# SIM808_SmartLock.net
KiCad netlist of a schematic drawn in Altium Designer
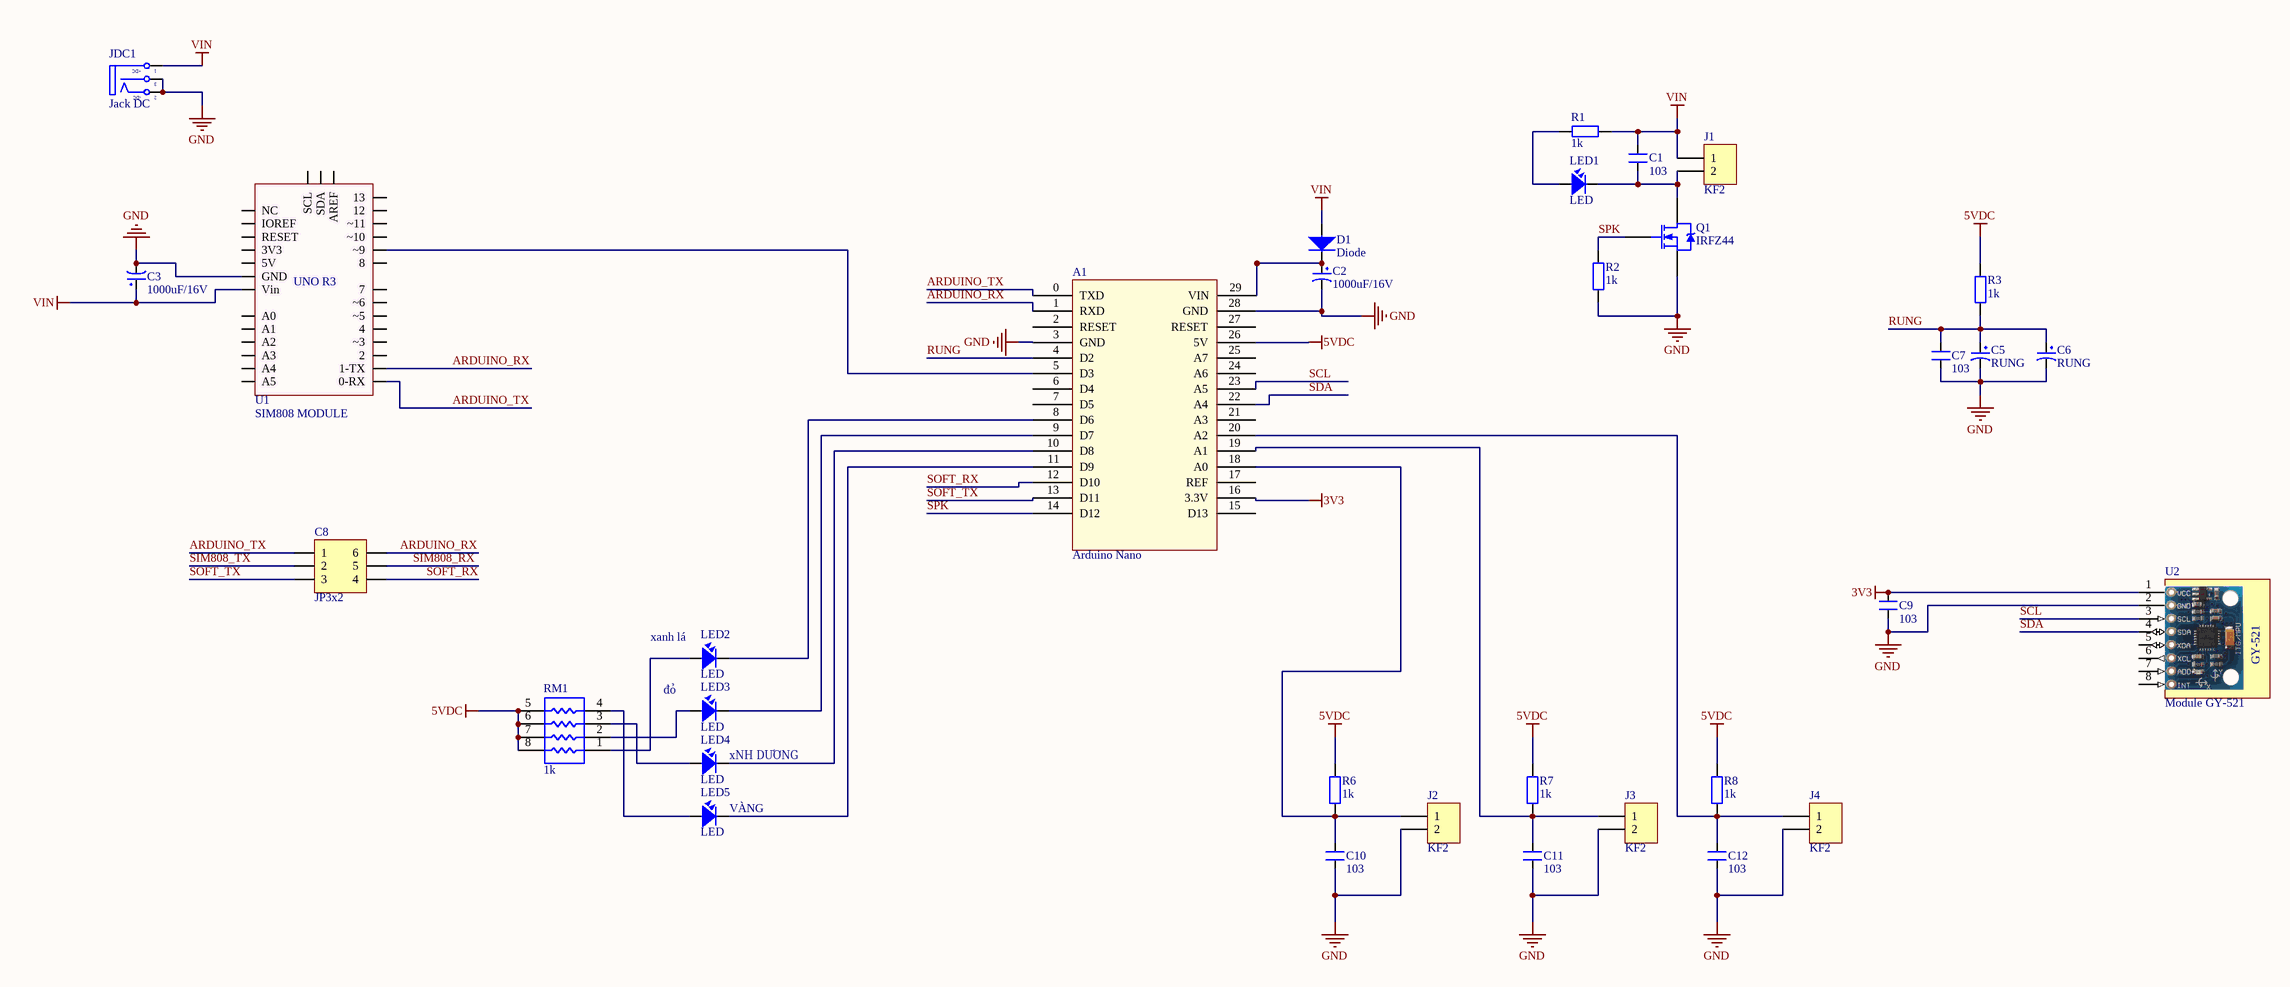
[diagram p0: SIM808_SmartLock.SchDoc]

(export (version "E")
  (design (tool "Eeschema 10.0.6"))
  (components
    (comp (ref "A1")
      (value "Arduino Nano")
      (footprint "Arduino Nano")
      (libsource (lib "OBIT_TESLA") (part "Arduino Nano"))
    )
    (comp (ref "C1")
      (value "103")
      (footprint "SM-0805")
      (description "Cap SMD")
      (libsource (lib "OBIT_TESLA") (part "CM"))
    )
    (comp (ref "C2")
      (value "1000uF/16V")
      (footprint "CP1.5/3.4")
      (description "Cap 1000uF/16V - 220uF/50V")
      (libsource (lib "OBIT_TESLA") (part "CP4"))
    )
    (comp (ref "C3")
      (value "1000uF/16V")
      (footprint "CP1.5/3.4")
      (description "Cap 1000uF/16V - 220uF/50V")
      (libsource (lib "OBIT_TESLA") (part "CP4"))
    )
    (comp (ref "C5")
      (value "RUNG")
      (footprint "CP1.5/3.4")
      (description "Cap 1000uF/16V - 220uF/50V")
      (libsource (lib "OBIT_TESLA") (part "CP4"))
    )
    (comp (ref "C6")
      (value "RUNG")
      (footprint "CP1.5/3.4")
      (description "Cap 1000uF/16V - 220uF/50V")
      (libsource (lib "OBIT_TESLA") (part "CP4"))
    )
    (comp (ref "C7")
      (value "103")
      (footprint "SM-0805")
      (description "Cap SMD")
      (libsource (lib "OBIT_TESLA") (part "CM"))
    )
    (comp (ref "C8")
      (value "JP3x2")
      (footprint "JP3-D2T")
      (description "WR-PHD 2.54 mm Dual Socket Header")
      (fields
        (field (name "MANUFACTURER") "Würth Elektronik eiSos GmbH")
        (field (name "PARTNO") "61300621821")
        (field (name "CREATED BY") "Karrer Zheng")
      )
      (libsource (lib "OBIT_TESLA") (part "JP3x2"))
    )
    (comp (ref "C9")
      (value "103")
      (footprint "SM-0805")
      (description "Cap SMD")
      (libsource (lib "OBIT_TESLA") (part "CM"))
    )
    (comp (ref "C10")
      (value "103")
      (footprint "SM-0805")
      (description "Cap SMD")
      (libsource (lib "OBIT_TESLA") (part "CM"))
    )
    (comp (ref "C11")
      (value "103")
      (footprint "SM-0805")
      (description "Cap SMD")
      (libsource (lib "OBIT_TESLA") (part "CM"))
    )
    (comp (ref "C12")
      (value "103")
      (footprint "SM-0805")
      (description "Cap SMD")
      (libsource (lib "OBIT_TESLA") (part "CM"))
    )
    (comp (ref "D1") (value "Diode") (footprint "DIO-SMD-106") (libsource (lib "OBIT_TESLA") (part "Diode")))
    (comp (ref "J1")
      (value "KF2")
      (footprint "KF2-5.08")
      (fields
        (field (name "MANUFACTURER") "Würth Elektronik eiSos GmbH")
        (field (name "PARTNO") "691103110002")
        (field (name "CREATED BY") "Karrer Zheng")
      )
      (libsource (lib "OBIT_TESLA") (part "KF2"))
    )
    (comp (ref "J2")
      (value "KF2")
      (footprint "KF2-5.08")
      (fields
        (field (name "MANUFACTURER") "Würth Elektronik eiSos GmbH")
        (field (name "PARTNO") "691103110002")
        (field (name "CREATED BY") "Karrer Zheng")
      )
      (libsource (lib "OBIT_TESLA") (part "KF2"))
    )
    (comp (ref "J3")
      (value "KF2")
      (footprint "KF2-5.08")
      (fields
        (field (name "MANUFACTURER") "Würth Elektronik eiSos GmbH")
        (field (name "PARTNO") "691103110002")
        (field (name "CREATED BY") "Karrer Zheng")
      )
      (libsource (lib "OBIT_TESLA") (part "KF2"))
    )
    (comp (ref "J4")
      (value "KF2")
      (footprint "KF2-5.08")
      (fields
        (field (name "MANUFACTURER") "Würth Elektronik eiSos GmbH")
        (field (name "PARTNO") "691103110002")
        (field (name "CREATED BY") "Karrer Zheng")
      )
      (libsource (lib "OBIT_TESLA") (part "KF2"))
    )
    (comp (ref "JDC1") (value "Jack DC") (footprint "DC0") (libsource (lib "OBIT_TESLA") (part "JACK_DC")))
    (comp (ref "LED1") (value "LED") (footprint "LED-5-BLUE") (libsource (lib "OBIT_TESLA") (part "LED")))
    (comp (ref "LED2") (value "LED") (footprint "LED-5-BLUE") (libsource (lib "OBIT_TESLA") (part "LED")))
    (comp (ref "LED3") (value "LED") (footprint "LED-5-BLUE") (libsource (lib "OBIT_TESLA") (part "LED")))
    (comp (ref "LED4") (value "LED") (footprint "LED-5-BLUE") (libsource (lib "OBIT_TESLA") (part "LED")))
    (comp (ref "LED5") (value "LED") (footprint "LED-5-BLUE") (libsource (lib "OBIT_TESLA") (part "LED")))
    (comp (ref "Q1") (value "IRFZ44") (footprint "TO252-123") (libsource (lib "OBIT_TESLA") (part "IRFZ44")))
    (comp (ref "R1")
      (value "1k")
      (footprint "RES-1/4W")
      (description "Resistor R1/4W")
      (libsource (lib "OBIT_TESLA") (part "R"))
    )
    (comp (ref "R2")
      (value "1k")
      (footprint "RES-1/4W")
      (description "Resistor R1/4W")
      (libsource (lib "OBIT_TESLA") (part "R"))
    )
    (comp (ref "R3")
      (value "1k")
      (footprint "RES-1/4W")
      (description "Resistor R1/4W")
      (libsource (lib "OBIT_TESLA") (part "R"))
    )
    (comp (ref "R6")
      (value "1k")
      (footprint "RES-1/4W")
      (description "Resistor R1/4W")
      (libsource (lib "OBIT_TESLA") (part "R"))
    )
    (comp (ref "R7")
      (value "1k")
      (footprint "RES-1/4W")
      (description "Resistor R1/4W")
      (libsource (lib "OBIT_TESLA") (part "R"))
    )
    (comp (ref "R8")
      (value "1k")
      (footprint "RES-1/4W")
      (description "Resistor R1/4W")
      (libsource (lib "OBIT_TESLA") (part "R"))
    )
    (comp (ref "RM1") (value "1k") (footprint "RN4-0805") (libsource (lib "OBIT_TESLA") (part "ResPack")))
    (comp (ref "U1")
      (value "SIM808 MODULE")
      (footprint "Arduino UNO R3")
      (description "ARDUINO  R3 ATMEGA328, ARDUINO UNO, EVAL BOARD")
      (libsource (lib "MCU") (part "KIT ARDUINO R3"))
    )
    (comp (ref "U2")
      (value "Module GY-521")
      (footprint "MODULE GY-9150")
      (description "MPU 6050")
      (libsource (lib "AltiumLibraryTieuBao (1)") (part "Module GY-521"))
    )
  )
  (nets
    (net (code "1") (name "/ARDUINO_RX") (class "Default")
      (node (ref "A1") (pin "1") (pinfunction "RXD_1") (pintype "passive"))
      (node (ref "C8") (pin "6") (pinfunction "6_6") (pintype "passive"))
      (node (ref "U1") (pin "1-TX") (pinfunction "1-TX_1-TX") (pintype "passive"))
    )
    (net (code "2") (name "/ARDUINO_TX") (class "Default")
      (node (ref "A1") (pin "0") (pinfunction "TXD_0") (pintype "passive"))
      (node (ref "C8") (pin "1") (pinfunction "1_1") (pintype "passive"))
      (node (ref "U1") (pin "0-RX") (pinfunction "0-RX_0-RX") (pintype "passive"))
    )
    (net (code "3") (name "/RUNG") (class "Default")
      (node (ref "A1") (pin "4") (pinfunction "D2_4") (pintype "passive"))
      (node (ref "C5") (pin "1") (pinfunction "1_1") (pintype "passive"))
      (node (ref "C6") (pin "1") (pinfunction "1_1") (pintype "passive"))
      (node (ref "C7") (pin "2") (pinfunction "2_2") (pintype "passive"))
      (node (ref "R3") (pin "1") (pinfunction "1_1") (pintype "passive"))
    )
    (net (code "4") (name "/SCL") (class "Default")
      (node (ref "A1") (pin "23") (pinfunction "A5_23") (pintype "passive"))
      (node (ref "U2") (pin "3") (pinfunction "SCL_3") (pintype "input"))
    )
    (net (code "5") (name "/SDA") (class "Default")
      (node (ref "A1") (pin "22") (pinfunction "A4_22") (pintype "passive"))
      (node (ref "U2") (pin "4") (pinfunction "SDA_4") (pintype "bidirectional"))
    )
    (net (code "6") (name "/SIM808_RX") (class "Default")
      (node (ref "C8") (pin "5") (pinfunction "5_5") (pintype "passive"))
    )
    (net (code "7") (name "/SIM808_TX") (class "Default")
      (node (ref "C8") (pin "2") (pinfunction "2_2") (pintype "passive"))
    )
    (net (code "8") (name "/SOFT_RX") (class "Default")
      (node (ref "A1") (pin "12") (pinfunction "D10_12") (pintype "passive"))
      (node (ref "C8") (pin "4") (pinfunction "4_4") (pintype "passive"))
    )
    (net (code "9") (name "/SOFT_TX") (class "Default")
      (node (ref "A1") (pin "13") (pinfunction "D11_13") (pintype "passive"))
      (node (ref "C8") (pin "3") (pinfunction "3_3") (pintype "passive"))
    )
    (net (code "10") (name "/SPK") (class "Default")
      (node (ref "A1") (pin "14") (pinfunction "D12_14") (pintype "passive"))
      (node (ref "Q1") (pin "1") (pinfunction "G_1") (pintype "passive"))
      (node (ref "R2") (pin "2") (pinfunction "2_2") (pintype "passive"))
    )
    (net (code "11") (name "3V3") (class "Default")
      (node (ref "A1") (pin "16") (pinfunction "3.3V_16") (pintype "passive"))
      (node (ref "C9") (pin "2") (pinfunction "2_2") (pintype "passive"))
      (node (ref "U2") (pin "1") (pinfunction "VCC_1") (pintype "power_in"))
    )
    (net (code "12") (name "5VDC") (class "Default")
      (node (ref "A1") (pin "26") (pinfunction "5V_26") (pintype "passive"))
      (node (ref "R3") (pin "2") (pinfunction "2_2") (pintype "passive"))
      (node (ref "R6") (pin "2") (pinfunction "2_2") (pintype "passive"))
      (node (ref "R7") (pin "2") (pinfunction "2_2") (pintype "passive"))
      (node (ref "R8") (pin "2") (pinfunction "2_2") (pintype "passive"))
      (node (ref "RM1") (pin "5") (pinfunction "5_5") (pintype "passive"))
      (node (ref "RM1") (pin "6") (pinfunction "6_6") (pintype "passive"))
      (node (ref "RM1") (pin "7") (pinfunction "7_7") (pintype "passive"))
      (node (ref "RM1") (pin "8") (pinfunction "8_8") (pintype "passive"))
    )
    (net (code "13") (name "GND") (class "Default")
      (node (ref "A1") (pin "28") (pinfunction "GND_28") (pintype "passive"))
      (node (ref "A1") (pin "3") (pinfunction "GND_3") (pintype "passive"))
      (node (ref "C10") (pin "1") (pinfunction "1_1") (pintype "passive"))
      (node (ref "C11") (pin "1") (pinfunction "1_1") (pintype "passive"))
      (node (ref "C12") (pin "1") (pinfunction "1_1") (pintype "passive"))
      (node (ref "C2") (pin "2") (pinfunction "2_2") (pintype "passive"))
      (node (ref "C3") (pin "2") (pinfunction "2_2") (pintype "passive"))
      (node (ref "C5") (pin "2") (pinfunction "2_2") (pintype "passive"))
      (node (ref "C6") (pin "2") (pinfunction "2_2") (pintype "passive"))
      (node (ref "C7") (pin "1") (pinfunction "1_1") (pintype "passive"))
      (node (ref "C9") (pin "1") (pinfunction "1_1") (pintype "passive"))
      (node (ref "J2") (pin "2") (pinfunction "2_2") (pintype "passive"))
      (node (ref "J3") (pin "2") (pinfunction "2_2") (pintype "passive"))
      (node (ref "J4") (pin "2") (pinfunction "2_2") (pintype "passive"))
      (node (ref "JDC1") (pin "2") (pinfunction "TN_2") (pintype "passive"))
      (node (ref "JDC1") (pin "3") (pinfunction "S_3") (pintype "power_in"))
      (node (ref "Q1") (pin "3") (pinfunction "S_3") (pintype "passive"))
      (node (ref "R2") (pin "1") (pinfunction "1_1") (pintype "passive"))
      (node (ref "U1") (pin "GND") (pinfunction "GND_GND") (pintype "passive"))
      (node (ref "U2") (pin "2") (pinfunction "GND_2") (pintype "power_in"))
    )
    (net (code "14") (name "Net-(A1-A0)") (class "Default")
      (node (ref "A1") (pin "18") (pinfunction "A0_18") (pintype "passive"))
      (node (ref "C10") (pin "2") (pinfunction "2_2") (pintype "passive"))
      (node (ref "J2") (pin "1") (pinfunction "1_1") (pintype "passive"))
      (node (ref "R6") (pin "1") (pinfunction "1_1") (pintype "passive"))
    )
    (net (code "15") (name "Net-(A1-A1)") (class "Default")
      (node (ref "A1") (pin "19") (pinfunction "A1_19") (pintype "passive"))
      (node (ref "C11") (pin "2") (pinfunction "2_2") (pintype "passive"))
      (node (ref "J3") (pin "1") (pinfunction "1_1") (pintype "passive"))
      (node (ref "R7") (pin "1") (pinfunction "1_1") (pintype "passive"))
    )
    (net (code "16") (name "Net-(A1-A2)") (class "Default")
      (node (ref "A1") (pin "20") (pinfunction "A2_20") (pintype "passive"))
      (node (ref "C12") (pin "2") (pinfunction "2_2") (pintype "passive"))
      (node (ref "J4") (pin "1") (pinfunction "1_1") (pintype "passive"))
      (node (ref "R8") (pin "1") (pinfunction "1_1") (pintype "passive"))
    )
    (net (code "17") (name "Net-(A1-D3)") (class "Default")
      (node (ref "A1") (pin "5") (pinfunction "D3_5") (pintype "passive"))
      (node (ref "U1") (pin "~9") (pinfunction "~9_~9") (pintype "passive"))
    )
    (net (code "18") (name "Net-(A1-D6)") (class "Default")
      (node (ref "A1") (pin "8") (pinfunction "D6_8") (pintype "passive"))
      (node (ref "LED2") (pin "2") (pinfunction "2_2") (pintype "passive"))
    )
    (net (code "19") (name "Net-(A1-D7)") (class "Default")
      (node (ref "A1") (pin "9") (pinfunction "D7_9") (pintype "passive"))
      (node (ref "LED3") (pin "2") (pinfunction "2_2") (pintype "passive"))
    )
    (net (code "20") (name "Net-(A1-D8)") (class "Default")
      (node (ref "A1") (pin "10") (pinfunction "D8_10") (pintype "passive"))
      (node (ref "LED4") (pin "2") (pinfunction "2_2") (pintype "passive"))
    )
    (net (code "21") (name "Net-(A1-D9)") (class "Default")
      (node (ref "A1") (pin "11") (pinfunction "D9_11") (pintype "passive"))
      (node (ref "LED5") (pin "2") (pinfunction "2_2") (pintype "passive"))
    )
    (net (code "22") (name "Net-(A1-VIN)") (class "Default")
      (node (ref "A1") (pin "29") (pinfunction "VIN_29") (pintype "passive"))
      (node (ref "C2") (pin "1") (pinfunction "1_1") (pintype "passive"))
      (node (ref "D1") (pin "2") (pinfunction "2_2") (pintype "passive"))
    )
    (net (code "23") (name "Net-(LED1-Pad1)") (class "Default")
      (node (ref "LED1") (pin "1") (pinfunction "1_1") (pintype "passive"))
      (node (ref "R1") (pin "1") (pinfunction "1_1") (pintype "passive"))
    )
    (net (code "24") (name "Net-(LED2-Pad1)") (class "Default")
      (node (ref "LED2") (pin "1") (pinfunction "1_1") (pintype "passive"))
      (node (ref "RM1") (pin "1") (pinfunction "1_1") (pintype "passive"))
    )
    (net (code "25") (name "Net-(LED3-Pad1)") (class "Default")
      (node (ref "LED3") (pin "1") (pinfunction "1_1") (pintype "passive"))
      (node (ref "RM1") (pin "2") (pinfunction "2_2") (pintype "passive"))
    )
    (net (code "26") (name "Net-(LED4-Pad1)") (class "Default")
      (node (ref "LED4") (pin "1") (pinfunction "1_1") (pintype "passive"))
      (node (ref "RM1") (pin "3") (pinfunction "3_3") (pintype "passive"))
    )
    (net (code "27") (name "Net-(LED5-Pad1)") (class "Default")
      (node (ref "LED5") (pin "1") (pinfunction "1_1") (pintype "passive"))
      (node (ref "RM1") (pin "4") (pinfunction "4_4") (pintype "passive"))
    )
    (net (code "28") (name "Net-(Q1-D)") (class "Default")
      (node (ref "C1") (pin "1") (pinfunction "1_1") (pintype "passive"))
      (node (ref "J1") (pin "2") (pinfunction "2_2") (pintype "passive"))
      (node (ref "LED1") (pin "2") (pinfunction "2_2") (pintype "passive"))
      (node (ref "Q1") (pin "2") (pinfunction "D_2") (pintype "passive"))
    )
    (net (code "29") (name "VIN") (class "Default")
      (node (ref "C1") (pin "2") (pinfunction "2_2") (pintype "passive"))
      (node (ref "C3") (pin "1") (pinfunction "1_1") (pintype "passive"))
      (node (ref "D1") (pin "1") (pinfunction "1_1") (pintype "passive"))
      (node (ref "J1") (pin "1") (pinfunction "1_1") (pintype "passive"))
      (node (ref "JDC1") (pin "1") (pinfunction "T_1") (pintype "passive"))
      (node (ref "R1") (pin "2") (pinfunction "2_2") (pintype "passive"))
      (node (ref "U1") (pin "Vin") (pinfunction "Vin_Vin") (pintype "passive"))
    )
    (net (code "30") (name "unconnected-(A1-A3-Pad21)") (class "Default")
      (node (ref "A1") (pin "21") (pinfunction "A3_21") (pintype "passive"))
    )
    (net (code "31") (name "unconnected-(A1-A6-Pad24)") (class "Default")
      (node (ref "A1") (pin "24") (pinfunction "A6_24") (pintype "passive"))
    )
    (net (code "32") (name "unconnected-(A1-A7-Pad25)") (class "Default")
      (node (ref "A1") (pin "25") (pinfunction "A7_25") (pintype "passive"))
    )
    (net (code "33") (name "unconnected-(A1-D4-Pad6)") (class "Default")
      (node (ref "A1") (pin "6") (pinfunction "D4_6") (pintype "passive"))
    )
    (net (code "34") (name "unconnected-(A1-D5-Pad7)") (class "Default")
      (node (ref "A1") (pin "7") (pinfunction "D5_7") (pintype "passive"))
    )
    (net (code "35") (name "unconnected-(A1-D13-Pad15)") (class "Default")
      (node (ref "A1") (pin "15") (pinfunction "D13_15") (pintype "passive"))
    )
    (net (code "36") (name "unconnected-(A1-REF-Pad17)") (class "Default")
      (node (ref "A1") (pin "17") (pinfunction "REF_17") (pintype "passive"))
    )
    (net (code "37") (name "unconnected-(A1-RESET-Pad2)") (class "Default")
      (node (ref "A1") (pin "2") (pinfunction "RESET_2") (pintype "passive"))
    )
    (net (code "38") (name "unconnected-(A1-RESET-Pad27)") (class "Default")
      (node (ref "A1") (pin "27") (pinfunction "RESET_27") (pintype "passive"))
    )
    (net (code "39") (name "unconnected-(U1-Pad2)") (class "Default")
      (node (ref "U1") (pin "2") (pinfunction "2_2") (pintype "passive"))
    )
    (net (code "40") (name "unconnected-(U1-Pad3V3)") (class "Default")
      (node (ref "U1") (pin "3V3") (pinfunction "3V3_3V3") (pintype "passive"))
    )
    (net (code "41") (name "unconnected-(U1-Pad4)") (class "Default")
      (node (ref "U1") (pin "4") (pinfunction "4_4") (pintype "passive"))
    )
    (net (code "42") (name "unconnected-(U1-Pad5V)") (class "Default")
      (node (ref "U1") (pin "5V") (pinfunction "5V_5V") (pintype "passive"))
    )
    (net (code "43") (name "unconnected-(U1-Pad7)") (class "Default")
      (node (ref "U1") (pin "7") (pinfunction "7_7") (pintype "passive"))
    )
    (net (code "44") (name "unconnected-(U1-Pad8)") (class "Default")
      (node (ref "U1") (pin "8") (pinfunction "8_8") (pintype "passive"))
    )
    (net (code "45") (name "unconnected-(U1-Pad12)") (class "Default")
      (node (ref "U1") (pin "12") (pinfunction "12_12") (pintype "passive"))
    )
    (net (code "46") (name "unconnected-(U1-Pad13)") (class "Default")
      (node (ref "U1") (pin "13") (pinfunction "13_13") (pintype "passive"))
    )
    (net (code "47") (name "unconnected-(U1-PadA0)") (class "Default")
      (node (ref "U1") (pin "A0") (pinfunction "A0_A0") (pintype "passive"))
    )
    (net (code "48") (name "unconnected-(U1-PadA1)") (class "Default")
      (node (ref "U1") (pin "A1") (pinfunction "A1_A1") (pintype "passive"))
    )
    (net (code "49") (name "unconnected-(U1-PadA2)") (class "Default")
      (node (ref "U1") (pin "A2") (pinfunction "A2_A2") (pintype "passive"))
    )
    (net (code "50") (name "unconnected-(U1-PadA3)") (class "Default")
      (node (ref "U1") (pin "A3") (pinfunction "A3_A3") (pintype "passive"))
    )
    (net (code "51") (name "unconnected-(U1-PadA4)") (class "Default")
      (node (ref "U1") (pin "A4") (pinfunction "A4_A4") (pintype "passive"))
    )
    (net (code "52") (name "unconnected-(U1-PadA5)") (class "Default")
      (node (ref "U1") (pin "A5") (pinfunction "A5_A5") (pintype "passive"))
    )
    (net (code "53") (name "unconnected-(U1-PadAREF)") (class "Default")
      (node (ref "U1") (pin "AREF") (pinfunction "AREF_AREF") (pintype "passive"))
    )
    (net (code "54") (name "unconnected-(U1-PadIOREF)") (class "Default")
      (node (ref "U1") (pin "IOREF") (pinfunction "IOREF_IOREF") (pintype "passive"))
    )
    (net (code "55") (name "unconnected-(U1-PadNC)") (class "Default")
      (node (ref "U1") (pin "NC") (pinfunction "NC_NC") (pintype "passive"))
    )
    (net (code "56") (name "unconnected-(U1-PadRESET)") (class "Default")
      (node (ref "U1") (pin "RESET") (pinfunction "RESET_RESET") (pintype "passive"))
    )
    (net (code "57") (name "unconnected-(U1-PadSCL)") (class "Default")
      (node (ref "U1") (pin "SCL") (pinfunction "SCL_SCL") (pintype "passive"))
    )
    (net (code "58") (name "unconnected-(U1-PadSDA)") (class "Default")
      (node (ref "U1") (pin "SDA") (pinfunction "SDA_SDA") (pintype "passive"))
    )
    (net (code "59") (name "unconnected-(U1-Pad~3)") (class "Default")
      (node (ref "U1") (pin "~3") (pinfunction "~3_~3") (pintype "passive"))
    )
    (net (code "60") (name "unconnected-(U1-Pad~5)") (class "Default")
      (node (ref "U1") (pin "~5") (pinfunction "~5_~5") (pintype "passive"))
    )
    (net (code "61") (name "unconnected-(U1-Pad~6)") (class "Default")
      (node (ref "U1") (pin "~6") (pinfunction "~6_~6") (pintype "passive"))
    )
    (net (code "62") (name "unconnected-(U1-Pad~10)") (class "Default")
      (node (ref "U1") (pin "~10") (pinfunction "~10_~10") (pintype "passive"))
    )
    (net (code "63") (name "unconnected-(U1-Pad~11)") (class "Default")
      (node (ref "U1") (pin "~11") (pinfunction "~11_~11") (pintype "passive"))
    )
    (net (code "64") (name "unconnected-(U2-ADO-Pad7)") (class "Default")
      (node (ref "U2") (pin "7") (pinfunction "ADO_7") (pintype "input"))
    )
    (net (code "65") (name "unconnected-(U2-INT-Pad8)") (class "Default")
      (node (ref "U2") (pin "8") (pinfunction "INT_8") (pintype "input"))
    )
    (net (code "66") (name "unconnected-(U2-XCL-Pad6)") (class "Default")
      (node (ref "U2") (pin "6") (pinfunction "XCL_6") (pintype "output"))
    )
    (net (code "67") (name "unconnected-(U2-XDA-Pad5)") (class "Default")
      (node (ref "U2") (pin "5") (pinfunction "XDA_5") (pintype "bidirectional"))
    )
  )
)
